# shematic.net
KiCad netlist of a schematic drawn in EAGLE
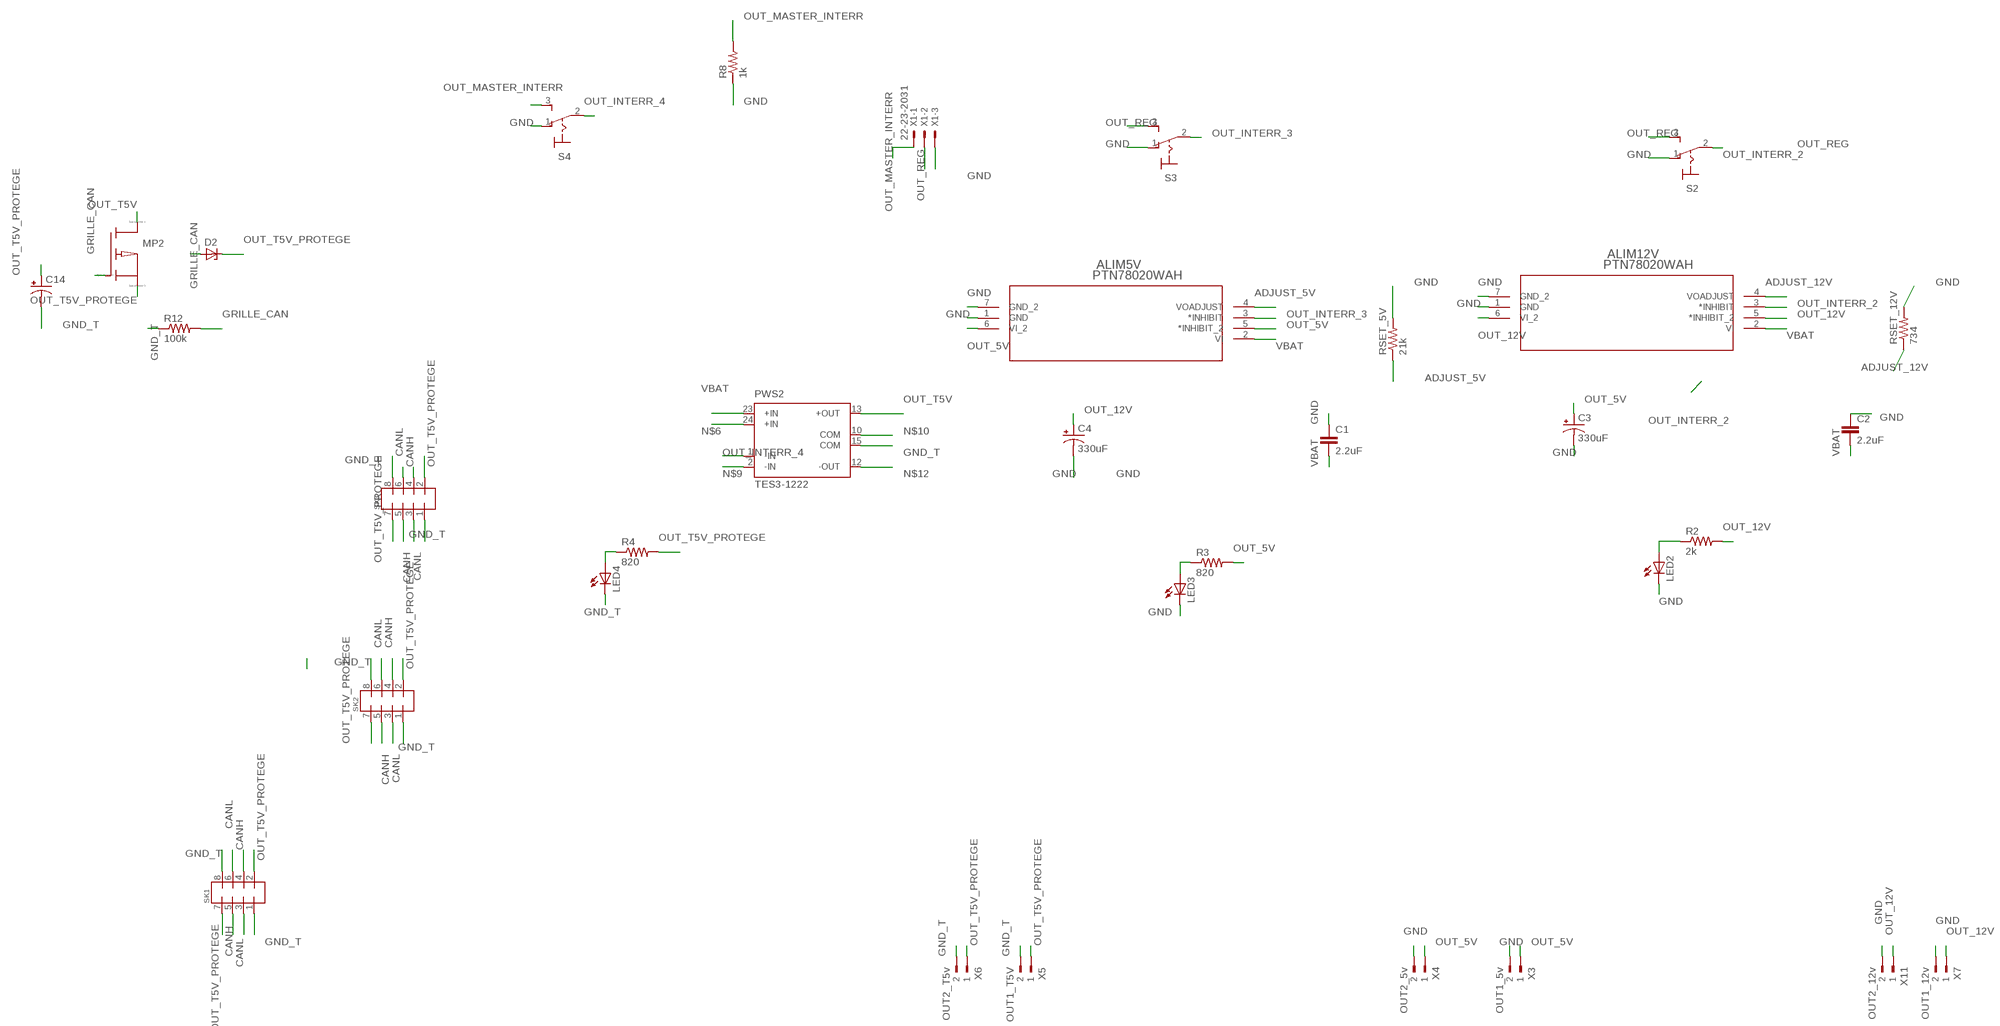
[diagram p0: schematic, sheet 1, part 1 of 2]
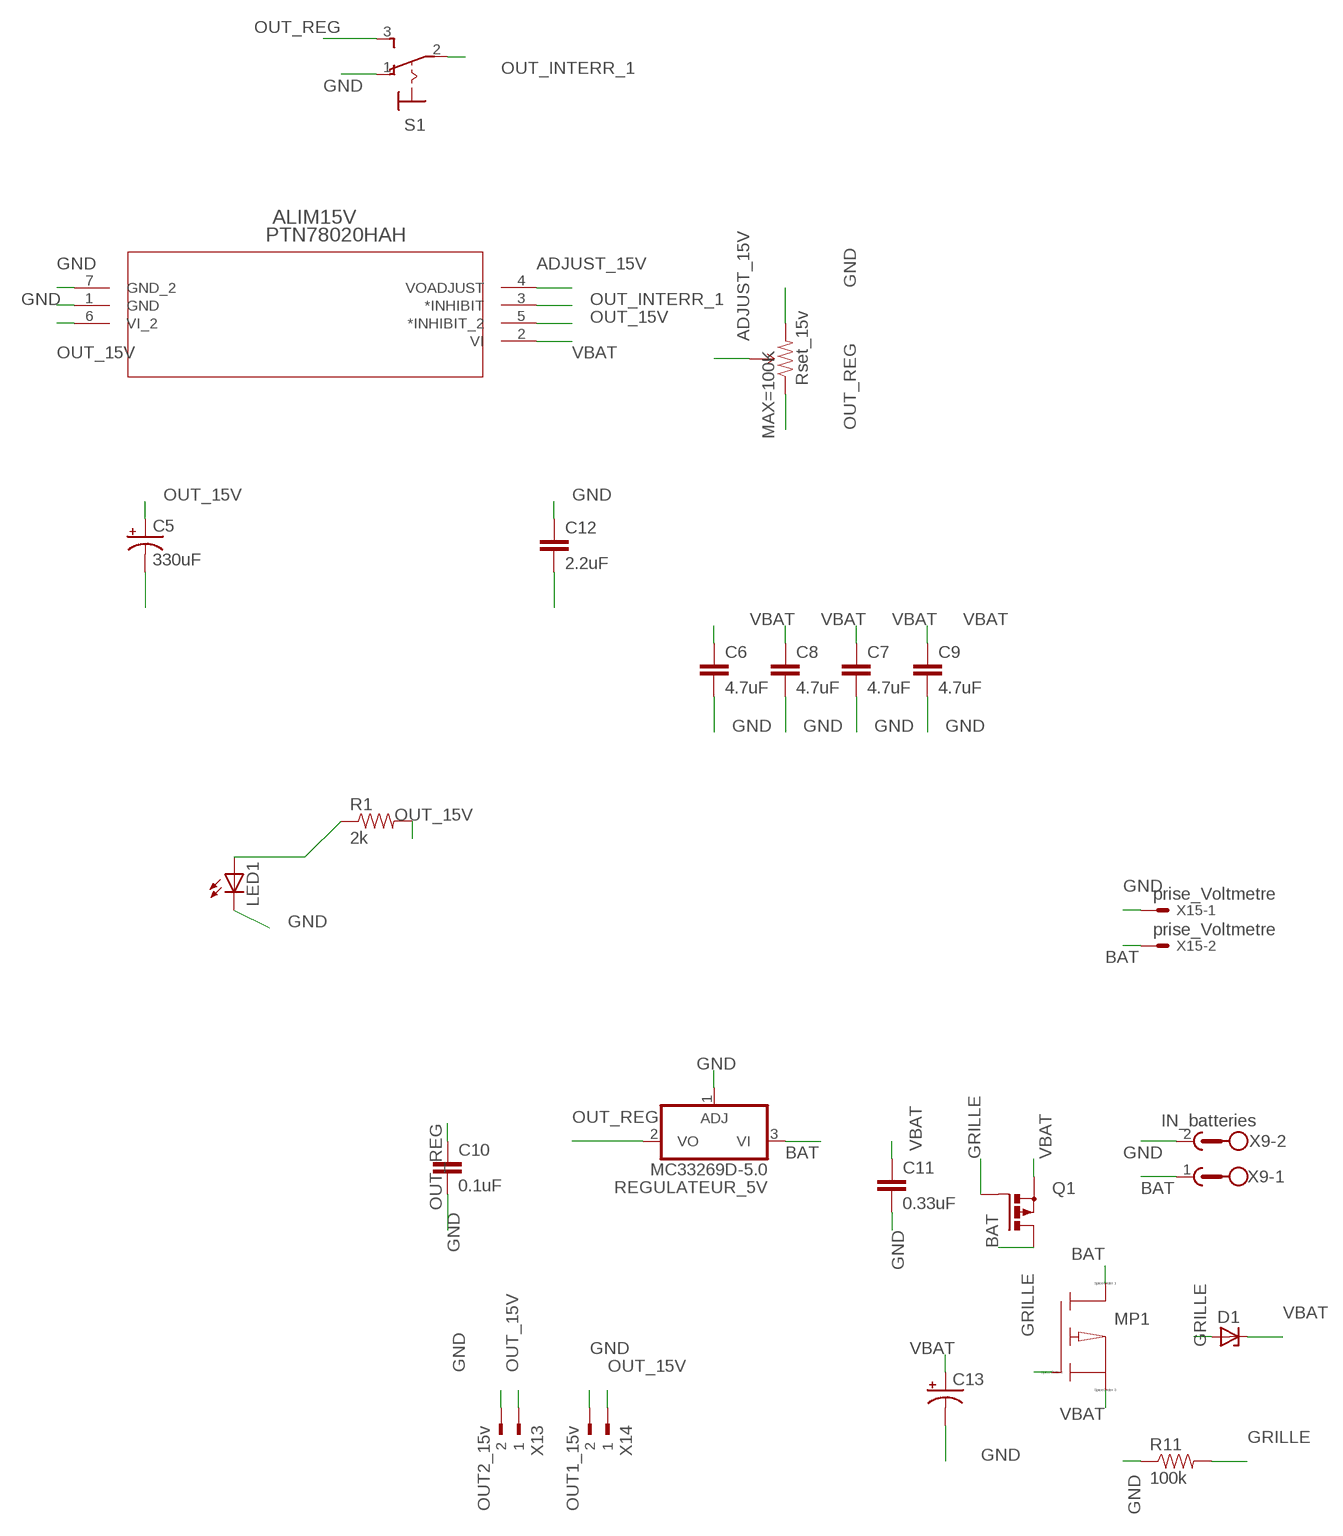
[diagram p1: schematic, sheet 1, part 2 of 2]

(export (version "E")
  (design (tool "Eeschema 10.0.6"))
  (components
    (comp (ref "ALIM5V")
      (value "PTN78020WAH")
      (footprint "eagle-import:EUK7")
      (libsource (lib "eagle-import") (part "PTN78020_"))
    )
    (comp (ref "ALIM12V")
      (value "PTN78020WAH")
      (footprint "eagle-import:EUK7")
      (libsource (lib "eagle-import") (part "PTN78020_"))
    )
    (comp (ref "ALIM15V")
      (value "PTN78020HAH")
      (footprint "eagle-import:EUK7")
      (libsource (lib "eagle-import") (part "PTN78020_"))
    )
    (comp (ref "C1")
      (value "2.2uF")
      (footprint "eagle-import:0805")
      (libsource (lib "eagle-import") (part "CAP0805"))
    )
    (comp (ref "C2")
      (value "2.2uF")
      (footprint "eagle-import:0805")
      (libsource (lib "eagle-import") (part "CAP0805"))
    )
    (comp (ref "C3")
      (value "330uF")
      (footprint "eagle-import:CPOL-RADIAL-100UF-25V")
      (libsource (lib "eagle-import") (part "CAP_POLPTH1"))
    )
    (comp (ref "C4")
      (value "330uF")
      (footprint "eagle-import:CPOL-RADIAL-100UF-25V")
      (libsource (lib "eagle-import") (part "CAP_POLPTH1"))
    )
    (comp (ref "C5")
      (value "330uF")
      (footprint "eagle-import:CPOL-RADIAL-100UF-25V")
      (libsource (lib "eagle-import") (part "CAP_POLPTH1"))
    )
    (comp (ref "C6")
      (value "4.7uF")
      (footprint "eagle-import:0805")
      (libsource (lib "eagle-import") (part "CAP0805"))
    )
    (comp (ref "C7")
      (value "4.7uF")
      (footprint "eagle-import:0805")
      (libsource (lib "eagle-import") (part "CAP0805"))
    )
    (comp (ref "C8")
      (value "4.7uF")
      (footprint "eagle-import:0805")
      (libsource (lib "eagle-import") (part "CAP0805"))
    )
    (comp (ref "C9")
      (value "4.7uF")
      (footprint "eagle-import:0805")
      (libsource (lib "eagle-import") (part "CAP0805"))
    )
    (comp (ref "C10")
      (value "0.1uF")
      (footprint "eagle-import:0805")
      (libsource (lib "eagle-import") (part "CAP0805"))
    )
    (comp (ref "C11")
      (value "0.33uF")
      (footprint "eagle-import:0805")
      (libsource (lib "eagle-import") (part "CAP0805"))
    )
    (comp (ref "C12")
      (value "2.2uF")
      (footprint "eagle-import:0805")
      (libsource (lib "eagle-import") (part "CAP0805"))
    )
    (comp (ref "C13")
      (value "CAP_POLPTH1")
      (footprint "eagle-import:CPOL-RADIAL-100UF-25V")
      (libsource (lib "eagle-import") (part "SparkFun-Passives_CAP_POLPTH1"))
    )
    (comp (ref "C14")
      (value "CAP_POLPTH1")
      (footprint "eagle-import:CPOL-RADIAL-100UF-25V")
      (libsource (lib "eagle-import") (part "SparkFun-Passives_CAP_POLPTH1"))
    )
    (comp (ref "D1")
      (value "ZENER-DIODESOT23")
      (footprint "eagle-import:SOT23")
      (libsource (lib "eagle-import") (part "ZENER-DIODESOT23"))
    )
    (comp (ref "D2")
      (value "ZENER-DIODESOT23")
      (footprint "eagle-import:SOT23")
      (libsource (lib "eagle-import") (part "ZENER-DIODESOT23"))
    )
    (comp (ref "LED1")
      (value "LEDCHIP-LED0805")
      (footprint "eagle-import:CHIP-LED0805")
      (libsource (lib "eagle-import") (part "LEDCHIP-LED0805"))
    )
    (comp (ref "LED2")
      (value "LEDCHIP-LED0805")
      (footprint "eagle-import:CHIP-LED0805")
      (libsource (lib "eagle-import") (part "LEDCHIP-LED0805"))
    )
    (comp (ref "LED3")
      (value "LEDCHIP-LED0805")
      (footprint "eagle-import:CHIP-LED0805")
      (libsource (lib "eagle-import") (part "LEDCHIP-LED0805"))
    )
    (comp (ref "LED4")
      (value "LEDCHIP-LED0805")
      (footprint "eagle-import:CHIP-LED0805")
      (libsource (lib "eagle-import") (part "LEDCHIP-LED0805"))
    )
    (comp (ref "MAX=100K")
      (value "Rset_15v")
      (footprint "eagle-import:3386U")
      (libsource (lib "eagle-import") (part "TRIMPOT-PTH-KNOB"))
    )
    (comp (ref "MP1")
      (value "PMOS")
      (footprint "eagle-import:SOT23")
      (libsource (lib "eagle-import") (part "PMOS"))
    )
    (comp (ref "MP2")
      (value "PMOS")
      (footprint "eagle-import:SOT23")
      (libsource (lib "eagle-import") (part "PMOS"))
    )
    (comp (ref "PWS2")
      (value "TES3-1222")
      (footprint "eagle-import:TES3")
      (libsource (lib "eagle-import") (part "TES3-1222"))
    )
    (comp (ref "Q1")
      (value "PMOSFET_PTO220BH")
      (footprint "eagle-import:TO220BH")
      (libsource (lib "eagle-import") (part "PMOSFET_PTO220BH"))
    )
    (comp (ref "R1")
      (value "2k")
      (footprint "eagle-import:0805")
      (libsource (lib "eagle-import") (part "SparkFun-Resistors_RESISTOR0805-RES"))
    )
    (comp (ref "R2")
      (value "2k")
      (footprint "eagle-import:0805")
      (libsource (lib "eagle-import") (part "SparkFun-Resistors_RESISTOR0805-RES"))
    )
    (comp (ref "R3")
      (value "820")
      (footprint "eagle-import:0805")
      (libsource (lib "eagle-import") (part "SparkFun-Resistors_RESISTOR0805-RES"))
    )
    (comp (ref "R4")
      (value "820")
      (footprint "eagle-import:0805")
      (libsource (lib "eagle-import") (part "SparkFun-Resistors_RESISTOR0805-RES"))
    )
    (comp (ref "R8")
      (value "1k")
      (footprint "eagle-import:0805")
      (libsource (lib "eagle-import") (part "SparkFun-Resistors_RESISTOR0805-RES"))
    )
    (comp (ref "R11")
      (value "100k")
      (footprint "eagle-import:0805")
      (libsource (lib "eagle-import") (part "RESISTOR0805-RES"))
    )
    (comp (ref "R12")
      (value "100k")
      (footprint "eagle-import:0805")
      (libsource (lib "eagle-import") (part "RESISTOR0805-RES"))
    )
    (comp (ref "REGULATEUR_5V")
      (value "MC33269D-5.0")
      (footprint "eagle-import:DPACK")
      (libsource (lib "eagle-import") (part "MC33269?D-5.0"))
    )
    (comp (ref "RSET_5V")
      (value "21k")
      (footprint "eagle-import:0805")
      (libsource (lib "eagle-import") (part "RESISTOR0805-RES"))
    )
    (comp (ref "RSET_12V")
      (value "734")
      (footprint "eagle-import:0805")
      (libsource (lib "eagle-import") (part "RESISTOR0805-RES"))
    )
    (comp (ref "S1")
      (value "M9040P")
      (footprint "eagle-import:M9040P")
      (libsource (lib "eagle-import") (part "M9040P"))
    )
    (comp (ref "S2")
      (value "M9040P")
      (footprint "eagle-import:M9040P")
      (libsource (lib "eagle-import") (part "M9040P"))
    )
    (comp (ref "S3")
      (value "M9040P")
      (footprint "eagle-import:M9040P")
      (libsource (lib "eagle-import") (part "M9040P"))
    )
    (comp (ref "S4")
      (value "M9040P")
      (footprint "eagle-import:M9040P")
      (libsource (lib "eagle-import") (part "M9040P"))
    )
    (comp (ref "SK1")
      (value "MMATCH-8-PTH")
      (footprint "eagle-import:AMP-215079-8")
      (libsource (lib "eagle-import") (part "MMATCH-8-PTH"))
    )
    (comp (ref "SK2")
      (value "MMATCH-8-PTH")
      (footprint "eagle-import:AMP-215079-8")
      (libsource (lib "eagle-import") (part "MMATCH-8-PTH"))
    )
    (comp (ref "SK3")
      (value "MMATCH-8-PTH")
      (footprint "eagle-import:AMP-215079-8")
      (libsource (lib "eagle-import") (part "MMATCH-8-PTH"))
    )
    (comp (ref "X1")
      (value "22-23-2031")
      (footprint "eagle-import:22-23-2031")
      (fields (field (name "MF") "MOLEX"))
      (libsource (lib "eagle-import") (part "22-23-2031"))
    )
    (comp (ref "X3")
      (value "OUT1_5v")
      (footprint "eagle-import:90-2")
      (libsource (lib "eagle-import") (part "90-2"))
    )
    (comp (ref "X4")
      (value "OUT2_5v")
      (footprint "eagle-import:90-2")
      (libsource (lib "eagle-import") (part "90-2"))
    )
    (comp (ref "X5")
      (value "OUT1_T5V")
      (footprint "eagle-import:90-2")
      (libsource (lib "eagle-import") (part "90-2"))
    )
    (comp (ref "X6")
      (value "OUT2_T5v")
      (footprint "eagle-import:90-2")
      (libsource (lib "eagle-import") (part "90-2"))
    )
    (comp (ref "X7")
      (value "OUT1_12v")
      (footprint "eagle-import:90-2")
      (libsource (lib "eagle-import") (part "90-2"))
    )
    (comp (ref "X9")
      (value "IN_batteries")
      (footprint "eagle-import:GMSTBA2")
      (fields (field (name "MF") "FARNELL") (field (name "MPN") "1757242"))
      (libsource (lib "eagle-import") (part "GMSTBA2"))
    )
    (comp (ref "X11")
      (value "OUT2_12v")
      (footprint "eagle-import:90-2")
      (libsource (lib "eagle-import") (part "90-2"))
    )
    (comp (ref "X13")
      (value "OUT2_15v")
      (footprint "eagle-import:90-2")
      (libsource (lib "eagle-import") (part "90-2"))
    )
    (comp (ref "X14")
      (value "OUT1_15v")
      (footprint "eagle-import:90-2")
      (libsource (lib "eagle-import") (part "90-2"))
    )
    (comp (ref "X15")
      (value "prise_Voltmetre")
      (footprint "eagle-import:KK-156-2")
      (libsource (lib "eagle-import") (part "KK-156-2"))
    )
  )
  (nets
    (net (code "1") (name "/ADJUST_5V") (class "Default")
      (node (ref "ALIM5V") (pin "4") (pinfunction "VOADJUST_4") (pintype "passive"))
      (node (ref "RSET_5V") (pin "1") (pinfunction "1_1") (pintype "passive"))
    )
    (net (code "2") (name "/ADJUST_12V") (class "Default")
      (node (ref "ALIM12V") (pin "4") (pinfunction "VOADJUST_4") (pintype "passive"))
      (node (ref "RSET_12V") (pin "1") (pinfunction "1_1") (pintype "passive"))
    )
    (net (code "3") (name "/ADJUST_15V") (class "Default")
      (node (ref "ALIM15V") (pin "4") (pinfunction "VOADJUST_4") (pintype "passive"))
      (node (ref "MAX=100K") (pin "2") (pinfunction "WIPER_2") (pintype "passive"))
    )
    (net (code "4") (name "/BAT") (class "Default")
      (node (ref "MP1") (pin "3") (pinfunction "D_3") (pintype "passive"))
      (node (ref "Q1") (pin "D") (pinfunction "D_D") (pintype "passive"))
      (node (ref "REGULATEUR_5V") (pin "3") (pinfunction "VI_3") (pintype "input"))
      (node (ref "X15") (pin "2") (pinfunction "S_2") (pintype "passive"))
      (node (ref "X9") (pin "1") (pinfunction "1_1") (pintype "passive"))
    )
    (net (code "5") (name "/CANH") (class "Default")
      (node (ref "SK1") (pin "4") (pinfunction "4_4") (pintype "bidirectional"))
      (node (ref "SK1") (pin "5") (pinfunction "5_5") (pintype "bidirectional"))
      (node (ref "SK2") (pin "4") (pinfunction "4_4") (pintype "bidirectional"))
      (node (ref "SK2") (pin "5") (pinfunction "5_5") (pintype "bidirectional"))
      (node (ref "SK3") (pin "4") (pinfunction "4_4") (pintype "bidirectional"))
      (node (ref "SK3") (pin "5") (pinfunction "5_5") (pintype "bidirectional"))
    )
    (net (code "6") (name "/CANL") (class "Default")
      (node (ref "SK1") (pin "3") (pinfunction "3_3") (pintype "bidirectional"))
      (node (ref "SK1") (pin "6") (pinfunction "6_6") (pintype "bidirectional"))
      (node (ref "SK2") (pin "3") (pinfunction "3_3") (pintype "bidirectional"))
      (node (ref "SK2") (pin "6") (pinfunction "6_6") (pintype "bidirectional"))
      (node (ref "SK3") (pin "3") (pinfunction "3_3") (pintype "bidirectional"))
      (node (ref "SK3") (pin "6") (pinfunction "6_6") (pintype "bidirectional"))
    )
    (net (code "7") (name "/GND") (class "Default")
      (node (ref "ALIM12V") (pin "1") (pinfunction "GND_1") (pintype "passive"))
      (node (ref "ALIM12V") (pin "7") (pinfunction "GND_2_7") (pintype "passive"))
      (node (ref "ALIM15V") (pin "1") (pinfunction "GND_1") (pintype "passive"))
      (node (ref "ALIM15V") (pin "7") (pinfunction "GND_2_7") (pintype "passive"))
      (node (ref "ALIM5V") (pin "1") (pinfunction "GND_1") (pintype "passive"))
      (node (ref "ALIM5V") (pin "7") (pinfunction "GND_2_7") (pintype "passive"))
      (node (ref "C1") (pin "1") (pinfunction "1_1") (pintype "passive"))
      (node (ref "C10") (pin "2") (pinfunction "2_2") (pintype "passive"))
      (node (ref "C11") (pin "2") (pinfunction "2_2") (pintype "passive"))
      (node (ref "C12") (pin "1") (pinfunction "1_1") (pintype "passive"))
      (node (ref "C13") (pin "2") (pinfunction "-_2") (pintype "passive"))
      (node (ref "C2") (pin "1") (pinfunction "1_1") (pintype "passive"))
      (node (ref "C3") (pin "2") (pinfunction "-_2") (pintype "passive"))
      (node (ref "C4") (pin "2") (pinfunction "-_2") (pintype "passive"))
      (node (ref "C5") (pin "2") (pinfunction "-_2") (pintype "passive"))
      (node (ref "C6") (pin "2") (pinfunction "2_2") (pintype "passive"))
      (node (ref "C7") (pin "2") (pinfunction "2_2") (pintype "passive"))
      (node (ref "C8") (pin "2") (pinfunction "2_2") (pintype "passive"))
      (node (ref "C9") (pin "2") (pinfunction "2_2") (pintype "passive"))
      (node (ref "LED1") (pin "C") (pinfunction "C_C") (pintype "passive"))
      (node (ref "LED2") (pin "C") (pinfunction "C_C") (pintype "passive"))
      (node (ref "LED3") (pin "C") (pinfunction "C_C") (pintype "passive"))
      (node (ref "MAX=100K") (pin "3") (pinfunction "CW_3") (pintype "passive"))
      (node (ref "R11") (pin "1") (pinfunction "1_1") (pintype "passive"))
      (node (ref "R8") (pin "1") (pinfunction "1_1") (pintype "passive"))
      (node (ref "REGULATEUR_5V") (pin "1") (pinfunction "ADJ_1") (pintype "input"))
      (node (ref "RSET_12V") (pin "2") (pinfunction "2_2") (pintype "passive"))
      (node (ref "RSET_5V") (pin "2") (pinfunction "2_2") (pintype "passive"))
      (node (ref "S1") (pin "1") (pinfunction "O_1") (pintype "passive"))
      (node (ref "S2") (pin "1") (pinfunction "O_1") (pintype "passive"))
      (node (ref "S3") (pin "1") (pinfunction "O_1") (pintype "passive"))
      (node (ref "S4") (pin "1") (pinfunction "O_1") (pintype "passive"))
      (node (ref "X1") (pin "3") (pinfunction "S_3") (pintype "passive"))
      (node (ref "X11") (pin "2") (pinfunction "2_2") (pintype "passive"))
      (node (ref "X13") (pin "2") (pinfunction "2_2") (pintype "passive"))
      (node (ref "X14") (pin "2") (pinfunction "2_2") (pintype "passive"))
      (node (ref "X15") (pin "1") (pinfunction "S_1") (pintype "passive"))
      (node (ref "X3") (pin "2") (pinfunction "2_2") (pintype "passive"))
      (node (ref "X4") (pin "2") (pinfunction "2_2") (pintype "passive"))
      (node (ref "X7") (pin "2") (pinfunction "2_2") (pintype "passive"))
      (node (ref "X9") (pin "2") (pinfunction "1_2") (pintype "passive"))
    )
    (net (code "8") (name "/GND_T") (class "Default")
      (node (ref "C14") (pin "2") (pinfunction "-_2") (pintype "passive"))
      (node (ref "LED4") (pin "C") (pinfunction "C_C") (pintype "passive"))
      (node (ref "PWS2") (pin "15") (pinfunction "COM_15") (pintype "passive"))
      (node (ref "R12") (pin "1") (pinfunction "1_1") (pintype "passive"))
      (node (ref "SK1") (pin "1") (pinfunction "1_1") (pintype "bidirectional"))
      (node (ref "SK1") (pin "8") (pinfunction "8_8") (pintype "bidirectional"))
      (node (ref "SK2") (pin "1") (pinfunction "1_1") (pintype "bidirectional"))
      (node (ref "SK2") (pin "8") (pinfunction "8_8") (pintype "bidirectional"))
      (node (ref "SK3") (pin "1") (pinfunction "1_1") (pintype "bidirectional"))
      (node (ref "SK3") (pin "8") (pinfunction "8_8") (pintype "bidirectional"))
      (node (ref "X5") (pin "2") (pinfunction "2_2") (pintype "passive"))
      (node (ref "X6") (pin "2") (pinfunction "2_2") (pintype "passive"))
    )
    (net (code "9") (name "/GRILLE") (class "Default")
      (node (ref "D1") (pin "1") (pinfunction "A_1") (pintype "passive"))
      (node (ref "MP1") (pin "1") (pinfunction "G_1") (pintype "passive"))
      (node (ref "Q1") (pin "G") (pinfunction "G_G") (pintype "passive"))
      (node (ref "R11") (pin "2") (pinfunction "2_2") (pintype "passive"))
    )
    (net (code "10") (name "/GRILLE_CAN") (class "Default")
      (node (ref "D2") (pin "1") (pinfunction "A_1") (pintype "passive"))
      (node (ref "MP2") (pin "1") (pinfunction "G_1") (pintype "passive"))
      (node (ref "R12") (pin "2") (pinfunction "2_2") (pintype "passive"))
    )
    (net (code "11") (name "/N$6") (class "Default")
      (node (ref "PWS2") (pin "24") (pinfunction "+IN_24") (pintype "input"))
    )
    (net (code "12") (name "/N$9") (class "Default")
      (node (ref "PWS2") (pin "2") (pinfunction "-IN_2") (pintype "input"))
    )
    (net (code "13") (name "/N$10") (class "Default")
      (node (ref "PWS2") (pin "10") (pinfunction "COM_10") (pintype "passive"))
    )
    (net (code "14") (name "/N$12") (class "Default")
      (node (ref "PWS2") (pin "12") (pinfunction "-OUT_12") (pintype "output"))
    )
    (net (code "15") (name "/OUT_5V") (class "Default")
      (node (ref "ALIM5V") (pin "5") (pinfunction "*INHIBIT_2_5") (pintype "passive"))
      (node (ref "ALIM5V") (pin "6") (pinfunction "VI_2_6") (pintype "passive"))
      (node (ref "C3") (pin "1") (pinfunction "+_1") (pintype "passive"))
      (node (ref "R3") (pin "2") (pinfunction "2_2") (pintype "passive"))
      (node (ref "X3") (pin "1") (pinfunction "1_1") (pintype "passive"))
      (node (ref "X4") (pin "1") (pinfunction "1_1") (pintype "passive"))
    )
    (net (code "16") (name "/OUT_12V") (class "Default")
      (node (ref "ALIM12V") (pin "5") (pinfunction "*INHIBIT_2_5") (pintype "passive"))
      (node (ref "ALIM12V") (pin "6") (pinfunction "VI_2_6") (pintype "passive"))
      (node (ref "C4") (pin "1") (pinfunction "+_1") (pintype "passive"))
      (node (ref "R2") (pin "2") (pinfunction "2_2") (pintype "passive"))
      (node (ref "X11") (pin "1") (pinfunction "1_1") (pintype "passive"))
      (node (ref "X7") (pin "1") (pinfunction "1_1") (pintype "passive"))
    )
    (net (code "17") (name "/OUT_15V") (class "Default")
      (node (ref "ALIM15V") (pin "5") (pinfunction "*INHIBIT_2_5") (pintype "passive"))
      (node (ref "ALIM15V") (pin "6") (pinfunction "VI_2_6") (pintype "passive"))
      (node (ref "C5") (pin "1") (pinfunction "+_1") (pintype "passive"))
      (node (ref "R1") (pin "2") (pinfunction "2_2") (pintype "passive"))
      (node (ref "X13") (pin "1") (pinfunction "1_1") (pintype "passive"))
      (node (ref "X14") (pin "1") (pinfunction "1_1") (pintype "passive"))
    )
    (net (code "18") (name "/OUT_INTERR_1") (class "Default")
      (node (ref "ALIM15V") (pin "3") (pinfunction "*INHIBIT_3") (pintype "passive"))
      (node (ref "S1") (pin "2") (pinfunction "P_2") (pintype "passive"))
    )
    (net (code "19") (name "/OUT_INTERR_2") (class "Default")
      (node (ref "ALIM12V") (pin "3") (pinfunction "*INHIBIT_3") (pintype "passive"))
      (node (ref "S2") (pin "2") (pinfunction "P_2") (pintype "passive"))
    )
    (net (code "20") (name "/OUT_INTERR_3") (class "Default")
      (node (ref "ALIM5V") (pin "3") (pinfunction "*INHIBIT_3") (pintype "passive"))
      (node (ref "S3") (pin "2") (pinfunction "P_2") (pintype "passive"))
    )
    (net (code "21") (name "/OUT_INTERR_4") (class "Default")
      (node (ref "PWS2") (pin "1") (pinfunction "-IN_1") (pintype "input"))
      (node (ref "S4") (pin "2") (pinfunction "P_2") (pintype "passive"))
    )
    (net (code "22") (name "/OUT_MASTER_INTERR") (class "Default")
      (node (ref "R8") (pin "2") (pinfunction "2_2") (pintype "passive"))
      (node (ref "S4") (pin "3") (pinfunction "S_3") (pintype "passive"))
      (node (ref "X1") (pin "1") (pinfunction "S_1") (pintype "passive"))
    )
    (net (code "23") (name "/OUT_REG") (class "Default")
      (node (ref "C10") (pin "1") (pinfunction "1_1") (pintype "passive"))
      (node (ref "MAX=100K") (pin "1") (pinfunction "CCW_1") (pintype "passive"))
      (node (ref "REGULATEUR_5V") (pin "2") (pinfunction "VO_2") (pintype "passive"))
      (node (ref "S1") (pin "3") (pinfunction "S_3") (pintype "passive"))
      (node (ref "S2") (pin "3") (pinfunction "S_3") (pintype "passive"))
      (node (ref "S3") (pin "3") (pinfunction "S_3") (pintype "passive"))
      (node (ref "X1") (pin "2") (pinfunction "S_2") (pintype "passive"))
    )
    (net (code "24") (name "/OUT_T5V") (class "Default")
      (node (ref "MP2") (pin "3") (pinfunction "D_3") (pintype "passive"))
      (node (ref "PWS2") (pin "13") (pinfunction "+OUT_13") (pintype "output"))
    )
    (net (code "25") (name "/OUT_T5V_PROTEGE") (class "Default")
      (node (ref "C14") (pin "1") (pinfunction "+_1") (pintype "passive"))
      (node (ref "D2") (pin "3") (pinfunction "C_3") (pintype "passive"))
      (node (ref "MP2") (pin "2") (pinfunction "S_2") (pintype "passive"))
      (node (ref "R4") (pin "2") (pinfunction "2_2") (pintype "passive"))
      (node (ref "SK1") (pin "2") (pinfunction "2_2") (pintype "bidirectional"))
      (node (ref "SK1") (pin "7") (pinfunction "7_7") (pintype "bidirectional"))
      (node (ref "SK2") (pin "2") (pinfunction "2_2") (pintype "bidirectional"))
      (node (ref "SK2") (pin "7") (pinfunction "7_7") (pintype "bidirectional"))
      (node (ref "SK3") (pin "2") (pinfunction "2_2") (pintype "bidirectional"))
      (node (ref "SK3") (pin "7") (pinfunction "7_7") (pintype "bidirectional"))
      (node (ref "X5") (pin "1") (pinfunction "1_1") (pintype "passive"))
      (node (ref "X6") (pin "1") (pinfunction "1_1") (pintype "passive"))
    )
    (net (code "26") (name "/VBAT") (class "Default")
      (node (ref "ALIM12V") (pin "2") (pinfunction "VI_2") (pintype "passive"))
      (node (ref "ALIM15V") (pin "2") (pinfunction "VI_2") (pintype "passive"))
      (node (ref "ALIM5V") (pin "2") (pinfunction "VI_2") (pintype "passive"))
      (node (ref "C1") (pin "2") (pinfunction "2_2") (pintype "passive"))
      (node (ref "C11") (pin "1") (pinfunction "1_1") (pintype "passive"))
      (node (ref "C12") (pin "2") (pinfunction "2_2") (pintype "passive"))
      (node (ref "C13") (pin "1") (pinfunction "+_1") (pintype "passive"))
      (node (ref "C2") (pin "2") (pinfunction "2_2") (pintype "passive"))
      (node (ref "C6") (pin "1") (pinfunction "1_1") (pintype "passive"))
      (node (ref "C7") (pin "1") (pinfunction "1_1") (pintype "passive"))
      (node (ref "C8") (pin "1") (pinfunction "1_1") (pintype "passive"))
      (node (ref "C9") (pin "1") (pinfunction "1_1") (pintype "passive"))
      (node (ref "D1") (pin "3") (pinfunction "C_3") (pintype "passive"))
      (node (ref "MP1") (pin "2") (pinfunction "S_2") (pintype "passive"))
      (node (ref "PWS2") (pin "23") (pinfunction "+IN_23") (pintype "input"))
      (node (ref "Q1") (pin "S") (pinfunction "S_S") (pintype "passive"))
    )
    (net (code "27") (name "Net-(LED1-PadA)") (class "Default")
      (node (ref "LED1") (pin "A") (pinfunction "A_A") (pintype "passive"))
      (node (ref "R1") (pin "1") (pinfunction "1_1") (pintype "passive"))
    )
    (net (code "28") (name "Net-(LED2-PadA)") (class "Default")
      (node (ref "LED2") (pin "A") (pinfunction "A_A") (pintype "passive"))
      (node (ref "R2") (pin "1") (pinfunction "1_1") (pintype "passive"))
    )
    (net (code "29") (name "Net-(LED3-PadA)") (class "Default")
      (node (ref "LED3") (pin "A") (pinfunction "A_A") (pintype "passive"))
      (node (ref "R3") (pin "1") (pinfunction "1_1") (pintype "passive"))
    )
    (net (code "30") (name "Net-(LED4-PadA)") (class "Default")
      (node (ref "LED4") (pin "A") (pinfunction "A_A") (pintype "passive"))
      (node (ref "R4") (pin "1") (pinfunction "1_1") (pintype "passive"))
    )
  )
)
